# MONOPLACA_FINAL.net
KiCad netlist of a schematic drawn in Altium Designer
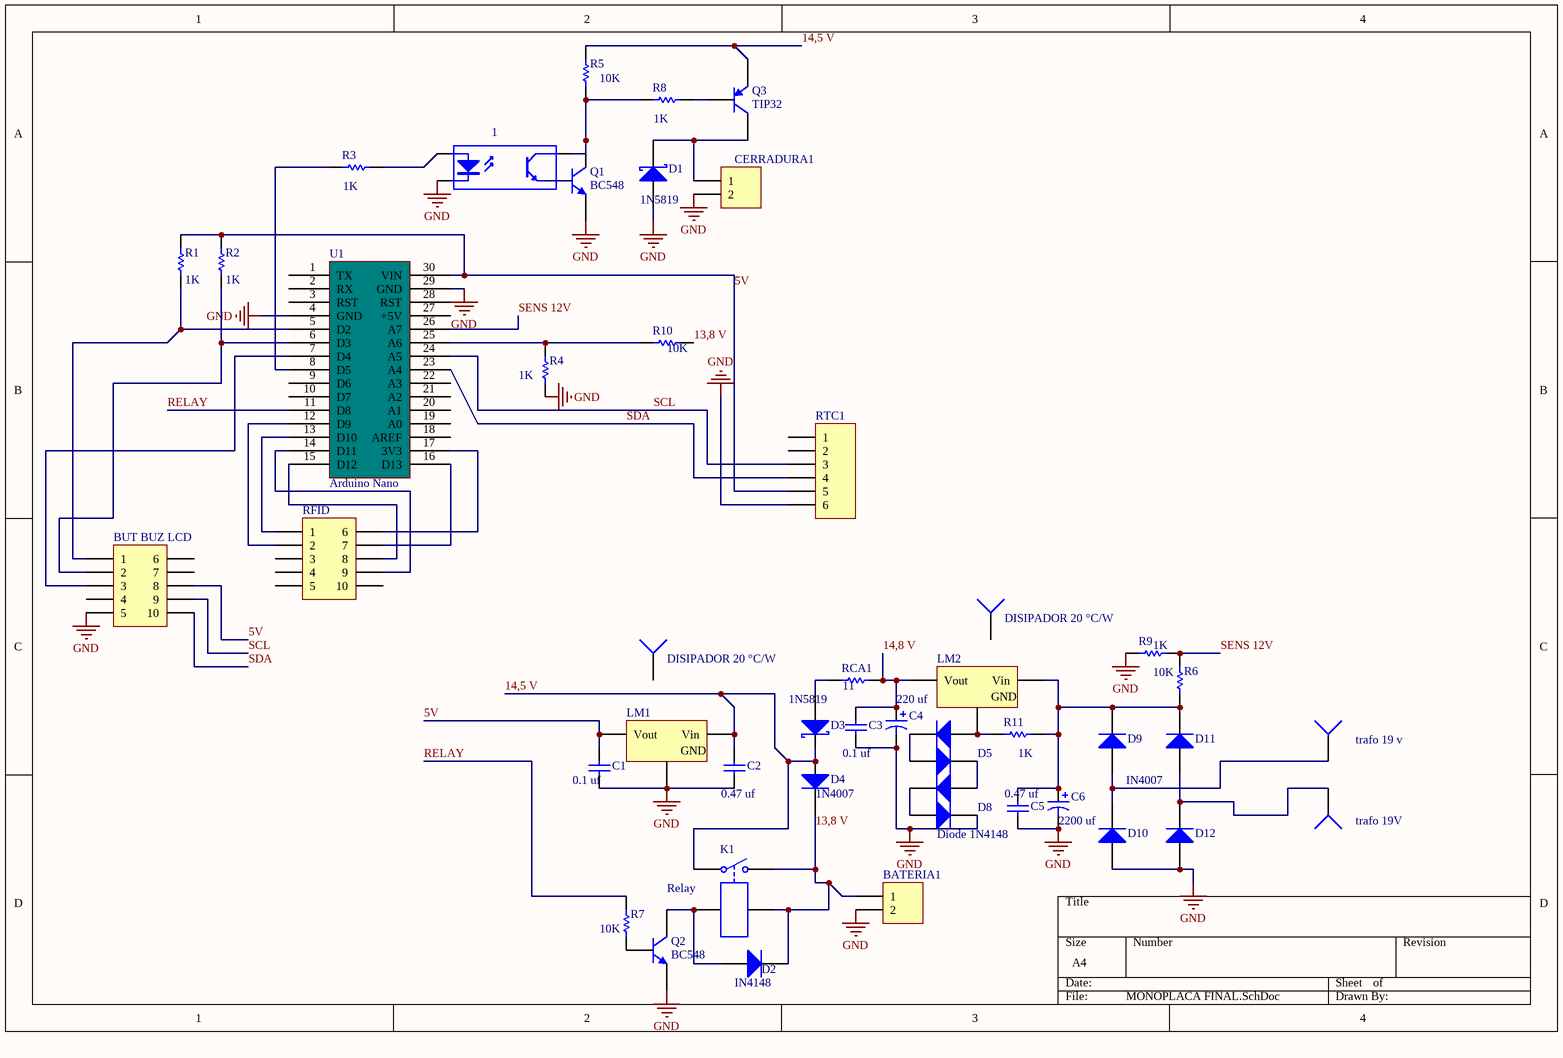
[diagram p0: MONOPLACA FINAL.SchDoc]

(export (version "E")
  (design (tool "Eeschema 10.0.6"))
  (components
    (comp (ref "1")
      (value "4N25")
      (footprint "DIP-6")
      (description "4-Pin Phototransistor Optocoupler")
      (fields (field (name "PUBLISHER") "Altium Limited"))
      (libsource (lib "altium-import") (part "root_0_Optoisolator1_"))
    )
    (comp (ref "BATERIA1")
      (value "Header 2")
      (footprint "Bornera 2 pin")
      (description "Header, 2-Pin")
      (fields (field (name "PUBLISHER") "Altium Limited"))
      (libsource (lib "Miscellaneous Connectors") (part "Header 2"))
    )
    (comp (ref "BUT BUZ LCD")
      (value "Header 5X2A")
      (footprint "HDR2X5_CEN")
      (description "Header, 5-Pin, Dual row")
      (fields (field (name "PUBLISHER") "Altium Limited"))
      (libsource (lib "Miscellaneous Connectors") (part "Header 5X2A"))
    )
    (comp (ref "C1")
      (value "0.1 uf")
      (footprint "CAP 5x12 mm")
      (description "Capacitor")
      (fields (field (name "Comment") "Cap") (field (name "PUBLISHER") "Altium Limited"))
      (libsource (lib "Miscellaneous Devices") (part "Cap"))
    )
    (comp (ref "C2")
      (value "0.47 uf")
      (footprint "CAP 12x10 mm")
      (description "Capacitor")
      (fields (field (name "Comment") "Cap") (field (name "PUBLISHER") "Altium Limited"))
      (libsource (lib "Miscellaneous Devices") (part "Cap"))
    )
    (comp (ref "C3")
      (value "0.1 uf")
      (footprint "CAP 5x12 mm")
      (description "Capacitor")
      (fields (field (name "Comment") "Cap") (field (name "PUBLISHER") "Altium Limited"))
      (libsource (lib "Miscellaneous Devices") (part "Cap"))
    )
    (comp (ref "C4")
      (value "220 uf")
      (footprint "CAP POL 3 - 8 mm")
      (description "Polarized Capacitor (Radial)")
      (fields (field (name "Comment") "Cap Pol1") (field (name "PUBLISHER") "Altium Limited"))
      (libsource (lib "Miscellaneous Devices") (part "Cap Pol1"))
    )
    (comp (ref "C5")
      (value "0.47 uf")
      (footprint "CAP 12x10 mm")
      (description "Capacitor")
      (fields (field (name "Comment") "Cap") (field (name "PUBLISHER") "Altium Limited"))
      (libsource (lib "Miscellaneous Devices") (part "Cap"))
    )
    (comp (ref "C6")
      (value "2200 uf")
      (footprint "CAP POL 18x7 mm")
      (description "Polarized Capacitor (Radial)")
      (fields (field (name "Comment") "Cap Pol1") (field (name "PUBLISHER") "Altium Limited"))
      (libsource (lib "Miscellaneous Devices") (part "Cap Pol1"))
    )
    (comp (ref "CERRADURA1")
      (value "Header 2")
      (footprint "Bornera 2 pin")
      (description "Header, 2-Pin")
      (fields (field (name "PUBLISHER") "Altium Limited"))
      (libsource (lib "Miscellaneous Connectors") (part "Header 2"))
    )
    (comp (ref "D1")
      (value "1N5819")
      (footprint "DO-41")
      (description "Schottky Diode")
      (fields (field (name "PUBLISHER") "Altium Limited"))
      (libsource (lib "Miscellaneous Devices") (part "D Schottky"))
    )
    (comp (ref "D2")
      (value "IN4148")
      (footprint "DO-35")
      (description "High Conductance Fast Diode")
      (fields (field (name "PUBLISHER") "Altium Limited"))
      (libsource (lib "Miscellaneous Devices") (part "Diode 1N914"))
    )
    (comp (ref "D3")
      (value "1N5819")
      (footprint "DO-41")
      (description "Schottky Diode")
      (fields (field (name "PUBLISHER") "Altium Limited"))
      (libsource (lib "Miscellaneous Devices") (part "D Schottky"))
    )
    (comp (ref "D4")
      (value "1N4007")
      (footprint "DO-41")
      (description "High Conductance Fast Diode")
      (fields (field (name "PUBLISHER") "Altium Limited"))
      (libsource (lib "Miscellaneous Devices") (part "Diode 1N914"))
    )
    (comp (ref "D5")
      (value "Diode 1N914")
      (footprint "DO-35")
      (description "High Conductance Fast Diode")
      (fields (field (name "PUBLISHER") "Altium Limited"))
      (libsource (lib "Miscellaneous Devices") (part "Diode 1N914"))
    )
    (comp (ref "D6")
      (value "Diode 1N914")
      (footprint "DO-35")
      (description "High Conductance Fast Diode")
      (fields (field (name "PUBLISHER") "Altium Limited"))
      (libsource (lib "Miscellaneous Devices") (part "Diode 1N914"))
    )
    (comp (ref "D7")
      (value "Diode 1N914")
      (footprint "DO-35")
      (description "High Conductance Fast Diode")
      (fields (field (name "PUBLISHER") "Altium Limited"))
      (libsource (lib "Miscellaneous Devices") (part "Diode 1N914"))
    )
    (comp (ref "D8")
      (value "Diode 1N4148")
      (footprint "DO-35")
      (description "High Conductance Fast Diode")
      (fields (field (name "PUBLISHER") "Altium Limited"))
      (libsource (lib "Miscellaneous Devices") (part "Diode 1N914"))
    )
    (comp (ref "D9")
      (value "IN4007")
      (footprint "DO-41")
      (description "High Conductance Fast Diode")
      (fields (field (name "PUBLISHER") "Altium Limited"))
      (libsource (lib "Miscellaneous Devices") (part "Diode 1N914"))
    )
    (comp (ref "D10")
      (value "IN4007")
      (footprint "DO-41")
      (description "High Conductance Fast Diode")
      (fields (field (name "PUBLISHER") "Altium Limited"))
      (libsource (lib "Miscellaneous Devices") (part "Diode 1N914"))
    )
    (comp (ref "D11")
      (value "IN4007")
      (footprint "DO-41")
      (description "High Conductance Fast Diode")
      (fields (field (name "PUBLISHER") "Altium Limited"))
      (libsource (lib "Miscellaneous Devices") (part "Diode 1N914"))
    )
    (comp (ref "D12")
      (value "IN4007")
      (footprint "DO-41")
      (description "High Conductance Fast Diode")
      (fields (field (name "PUBLISHER") "Altium Limited"))
      (libsource (lib "Miscellaneous Devices") (part "Diode 1N914"))
    )
    (comp (ref "DISIPADOR 1")
      (value "DISIPADOR 20 °C/W")
      (footprint "DISIPADOR 20 C°/W")
      (description "Socket")
      (fields (field (name "PUBLISHER") "Altium Limited"))
      (libsource (lib "Miscellaneous Connectors") (part "Socket"))
    )
    (comp (ref "DISIPADOR 2")
      (value "DISIPADOR 20 °C/W")
      (footprint "DISIPADOR 20 C°/W")
      (description "Socket")
      (fields (field (name "PUBLISHER") "Altium Limited"))
      (libsource (lib "Miscellaneous Connectors") (part "Socket"))
    )
    (comp (ref "J1")
      (value "trafo 19V")
      (footprint "PIN1")
      (description "Socket")
      (fields (field (name "PUBLISHER") "Altium Limited"))
      (libsource (lib "Miscellaneous Connectors") (part "Socket"))
    )
    (comp (ref "J2")
      (value "trafo 19 v")
      (footprint "PIN1")
      (description "Socket")
      (fields (field (name "PUBLISHER") "Altium Limited"))
      (libsource (lib "Miscellaneous Connectors") (part "Socket"))
    )
    (comp (ref "K1")
      (value "Relay")
      (footprint "RELE")
      (description "Single-Pole Single-Throw Relay")
      (fields (field (name "PUBLISHER") "Altium Limited"))
      (libsource (lib "Miscellaneous Devices") (part "Relay-SPST"))
    )
    (comp (ref "LM1")
      (value "LM7805")
      (footprint "TO-220AB")
      (description "Voltage Regulator")
      (fields (field (name "PUBLISHER") "Altium Limited"))
      (libsource (lib "Miscellaneous Devices") (part "Volt Reg"))
    )
    (comp (ref "LM2")
      (value "LM7812")
      (footprint "TO-220AB")
      (description "Voltage Regulator")
      (fields (field (name "PUBLISHER") "Altium Limited"))
      (libsource (lib "Miscellaneous Devices") (part "Volt Reg"))
    )
    (comp (ref "Q1")
      (value "BC548")
      (footprint "TO-92-MOD")
      (description "NPN General Purpose Amplifier")
      (fields (field (name "PUBLISHER") "Altium Limited"))
      (libsource (lib "Miscellaneous Devices") (part "2N3904"))
    )
    (comp (ref "Q2")
      (value "BC548")
      (footprint "TO-92-MOD")
      (description "NPN Bipolar Transistor")
      (fields (field (name "PUBLISHER") "Altium Limited"))
      (libsource (lib "Miscellaneous Devices") (part "NPN"))
    )
    (comp (ref "Q3")
      (value "TIP32")
      (footprint "TO-220AB")
      (description "PNP General Purpose Amplifier")
      (fields (field (name "PUBLISHER") "Altium Limited"))
      (libsource (lib "Miscellaneous Devices") (part "2N3906"))
    )
    (comp (ref "R1")
      (value "1K")
      (footprint "RESISTENCIA 0.25 W")
      (description "Resistor")
      (fields (field (name "Comment") "Res1") (field (name "PUBLISHER") "Altium Limited"))
      (libsource (lib "Miscellaneous Devices") (part "Res1"))
    )
    (comp (ref "R2")
      (value "1K")
      (footprint "RESISTENCIA 0.25 W")
      (description "Resistor")
      (fields (field (name "Comment") "Res1") (field (name "PUBLISHER") "Altium Limited"))
      (libsource (lib "Miscellaneous Devices") (part "Res1"))
    )
    (comp (ref "R3")
      (value "1K")
      (footprint "RESISTENCIA 0.25 W")
      (description "Resistor")
      (fields (field (name "Comment") "Res1") (field (name "PUBLISHER") "Altium Limited"))
      (libsource (lib "Miscellaneous Devices") (part "Res1"))
    )
    (comp (ref "R4")
      (value "1K")
      (footprint "RESISTENCIA 0.25 W")
      (description "Resistor")
      (fields (field (name "Comment") "Res1") (field (name "PUBLISHER") "Altium Limited"))
      (libsource (lib "Miscellaneous Devices") (part "Res1"))
    )
    (comp (ref "R5")
      (value "10K")
      (footprint "RESISTENCIA 0.25 W")
      (description "Resistor")
      (fields (field (name "Comment") "Res1") (field (name "PUBLISHER") "Altium Limited"))
      (libsource (lib "Miscellaneous Devices") (part "Res1"))
    )
    (comp (ref "R6")
      (value "10K")
      (footprint "RESISTENCIA 0.25 W")
      (description "Resistor")
      (fields (field (name "Comment") "Res1") (field (name "PUBLISHER") "Altium Limited"))
      (libsource (lib "Miscellaneous Devices") (part "Res1"))
    )
    (comp (ref "R7")
      (value "10K")
      (footprint "RESISTENCIA 0.25 W")
      (description "Resistor")
      (fields (field (name "Comment") "Res1") (field (name "PUBLISHER") "Altium Limited"))
      (libsource (lib "Miscellaneous Devices") (part "Res1"))
    )
    (comp (ref "R8")
      (value "1K")
      (footprint "RESISTENCIA 0.25 W")
      (description "Resistor")
      (fields (field (name "Comment") "Res1") (field (name "PUBLISHER") "Altium Limited"))
      (libsource (lib "Miscellaneous Devices") (part "Res1"))
    )
    (comp (ref "R9")
      (value "1K")
      (footprint "RESISTENCIA 0.25 W")
      (description "Resistor")
      (fields (field (name "Comment") "Res1") (field (name "PUBLISHER") "Altium Limited"))
      (libsource (lib "Miscellaneous Devices") (part "Res1"))
    )
    (comp (ref "R10")
      (value "10K")
      (footprint "RESISTENCIA 0.25 W")
      (description "Resistor")
      (fields (field (name "Comment") "Res1") (field (name "PUBLISHER") "Altium Limited"))
      (libsource (lib "Miscellaneous Devices") (part "Res1"))
    )
    (comp (ref "R11")
      (value "1K")
      (footprint "RESISTENCIA 0.25 W")
      (description "Resistor")
      (fields (field (name "Comment") "Res1") (field (name "PUBLISHER") "Altium Limited"))
      (libsource (lib "Miscellaneous Devices") (part "Res1"))
    )
    (comp (ref "RCA1")
      (value "11")
      (footprint "RESISTENCIA 5W")
      (description "Resistor")
      (fields (field (name "Comment") "Res1") (field (name "PUBLISHER") "Altium Limited"))
      (libsource (lib "Miscellaneous Devices") (part "Res1"))
    )
    (comp (ref "RFID")
      (value "Header 5X2A")
      (footprint "HDR2X5_CEN")
      (description "Header, 5-Pin, Dual row")
      (fields (field (name "PUBLISHER") "Altium Limited"))
      (libsource (lib "Miscellaneous Connectors") (part "Header 5X2A"))
    )
    (comp (ref "RTC1")
      (value "Header 6")
      (footprint "HDR1X6")
      (description "Header, 6-Pin")
      (fields (field (name "PUBLISHER") "Altium Limited"))
      (libsource (lib "Miscellaneous Connectors") (part "Header 6"))
    )
    (comp (ref "U1")
      (value "Arduino Nano")
      (footprint "Arduino nano")
      (libsource (lib "Nano") (part "Component_1"))
    )
  )
  (nets
    (net (code "1") (name "/5V") (class "Default")
      (node (ref "BUT BUZ LCD") (pin "8") (pinfunction "8_8") (pintype "passive"))
      (node (ref "C1") (pin "2") (pinfunction "2_2") (pintype "passive"))
      (node (ref "LM1") (pin "3") (pinfunction "Vout_3") (pintype "passive"))
      (node (ref "R1") (pin "2") (pinfunction "2_2") (pintype "passive"))
      (node (ref "R2") (pin "2") (pinfunction "2_2") (pintype "passive"))
      (node (ref "RTC1") (pin "5") (pinfunction "5_5") (pintype "passive"))
      (node (ref "U1") (pin "30") (pinfunction "VIN_30") (pintype "passive"))
    )
    (net (code "2") (name "/13,8 V") (class "Default")
      (node (ref "BATERIA1") (pin "1") (pinfunction "1_1") (pintype "passive"))
      (node (ref "D2") (pin "2") (pinfunction "K_2") (pintype "passive"))
      (node (ref "D4") (pin "2") (pinfunction "K_2") (pintype "passive"))
      (node (ref "K1") (pin "2") (pinfunction "2_2") (pintype "passive"))
      (node (ref "K1") (pin "4") (pinfunction "4_4") (pintype "passive"))
      (node (ref "R10") (pin "2") (pinfunction "2_2") (pintype "passive"))
    )
    (net (code "3") (name "/14,5 V") (class "Default")
      (node (ref "C2") (pin "2") (pinfunction "2_2") (pintype "passive"))
      (node (ref "D3") (pin "2") (pinfunction "K_2") (pintype "passive"))
      (node (ref "D4") (pin "1") (pinfunction "A_1") (pintype "passive"))
      (node (ref "K1") (pin "1") (pinfunction "1_1") (pintype "passive"))
      (node (ref "LM1") (pin "1") (pinfunction "Vin_1") (pintype "passive"))
      (node (ref "Q3") (pin "1") (pinfunction "E_1") (pintype "passive"))
      (node (ref "R5") (pin "2") (pinfunction "2_2") (pintype "passive"))
    )
    (net (code "4") (name "/14,8 V") (class "Default")
      (node (ref "C3") (pin "2") (pinfunction "2_2") (pintype "passive"))
      (node (ref "C4") (pin "1") (pinfunction "1_1") (pintype "passive"))
      (node (ref "LM2") (pin "3") (pinfunction "Vout_3") (pintype "passive"))
      (node (ref "RCA1") (pin "2") (pinfunction "2_2") (pintype "passive"))
    )
    (net (code "5") (name "/RELAY") (class "Default")
      (node (ref "R7") (pin "1") (pinfunction "1_1") (pintype "passive"))
      (node (ref "U1") (pin "11") (pinfunction "D8_11") (pintype "passive"))
    )
    (net (code "6") (name "/SCL") (class "Default")
      (node (ref "BUT BUZ LCD") (pin "9") (pinfunction "9_9") (pintype "passive"))
      (node (ref "RTC1") (pin "3") (pinfunction "3_3") (pintype "passive"))
      (node (ref "U1") (pin "24") (pinfunction "A5_24") (pintype "passive"))
    )
    (net (code "7") (name "/SDA") (class "Default")
      (node (ref "BUT BUZ LCD") (pin "10") (pinfunction "10_10") (pintype "passive"))
      (node (ref "RTC1") (pin "4") (pinfunction "4_4") (pintype "passive"))
      (node (ref "U1") (pin "23") (pinfunction "A4_23") (pintype "passive"))
    )
    (net (code "8") (name "/SENS 12V") (class "Default")
      (node (ref "R6") (pin "2") (pinfunction "2_2") (pintype "passive"))
      (node (ref "R9") (pin "2") (pinfunction "2_2") (pintype "passive"))
      (node (ref "U1") (pin "26") (pinfunction "A7_26") (pintype "passive"))
    )
    (net (code "9") (name "GND") (class "Default")
      (node (ref "1") (pin "2") (pinfunction "K_2") (pintype "passive"))
      (node (ref "BATERIA1") (pin "2") (pinfunction "2_2") (pintype "passive"))
      (node (ref "BUT BUZ LCD") (pin "5") (pinfunction "5_5") (pintype "passive"))
      (node (ref "C1") (pin "1") (pinfunction "1_1") (pintype "passive"))
      (node (ref "C2") (pin "1") (pinfunction "1_1") (pintype "passive"))
      (node (ref "C3") (pin "1") (pinfunction "1_1") (pintype "passive"))
      (node (ref "C4") (pin "2") (pinfunction "2_2") (pintype "passive"))
      (node (ref "C5") (pin "1") (pinfunction "1_1") (pintype "passive"))
      (node (ref "C6") (pin "2") (pinfunction "2_2") (pintype "passive"))
      (node (ref "CERRADURA1") (pin "2") (pinfunction "2_2") (pintype "passive"))
      (node (ref "D1") (pin "1") (pinfunction "A_1") (pintype "passive"))
      (node (ref "D10") (pin "1") (pinfunction "A_1") (pintype "passive"))
      (node (ref "D12") (pin "1") (pinfunction "A_1") (pintype "passive"))
      (node (ref "D8") (pin "2") (pinfunction "K_2") (pintype "passive"))
      (node (ref "LM1") (pin "2") (pinfunction "GND_2") (pintype "passive"))
      (node (ref "Q1") (pin "1") (pinfunction "E_1") (pintype "passive"))
      (node (ref "Q2") (pin "3") (pinfunction "E_3") (pintype "passive"))
      (node (ref "R4") (pin "1") (pinfunction "1_1") (pintype "passive"))
      (node (ref "R9") (pin "1") (pinfunction "1_1") (pintype "passive"))
      (node (ref "RTC1") (pin "6") (pinfunction "6_6") (pintype "passive"))
      (node (ref "U1") (pin "29") (pinfunction "GND_29") (pintype "passive"))
      (node (ref "U1") (pin "4") (pinfunction "GND_4") (pintype "passive"))
    )
    (net (code "10") (name "Net-(1-A)") (class "Default")
      (node (ref "1") (pin "1") (pinfunction "A_1") (pintype "passive"))
      (node (ref "R3") (pin "2") (pinfunction "2_2") (pintype "passive"))
    )
    (net (code "11") (name "Net-(1-C)") (class "Default")
      (node (ref "1") (pin "4") (pinfunction "C_4") (pintype "passive"))
      (node (ref "Q1") (pin "3") (pinfunction "C_3") (pintype "passive"))
      (node (ref "R5") (pin "1") (pinfunction "1_1") (pintype "passive"))
      (node (ref "R8") (pin "1") (pinfunction "1_1") (pintype "passive"))
    )
    (net (code "12") (name "Net-(1-E)") (class "Default")
      (node (ref "1") (pin "3") (pinfunction "E_3") (pintype "passive"))
      (node (ref "Q1") (pin "2") (pinfunction "B_2") (pintype "passive"))
    )
    (net (code "13") (name "Net-(D1-K)") (class "Default")
      (node (ref "CERRADURA1") (pin "1") (pinfunction "1_1") (pintype "passive"))
      (node (ref "D1") (pin "2") (pinfunction "K_2") (pintype "passive"))
      (node (ref "Q3") (pin "3") (pinfunction "C_3") (pintype "passive"))
    )
    (net (code "14") (name "Net-(D2-A)") (class "Default")
      (node (ref "D2") (pin "1") (pinfunction "A_1") (pintype "passive"))
      (node (ref "K1") (pin "3") (pinfunction "3_3") (pintype "passive"))
      (node (ref "Q2") (pin "1") (pinfunction "C_1") (pintype "passive"))
    )
    (net (code "15") (name "Net-(D3-A)") (class "Default")
      (node (ref "D3") (pin "1") (pinfunction "A_1") (pintype "passive"))
      (node (ref "RCA1") (pin "1") (pinfunction "1_1") (pintype "passive"))
    )
    (net (code "16") (name "Net-(D5-A)") (class "Default")
      (node (ref "D5") (pin "1") (pinfunction "A_1") (pintype "passive"))
      (node (ref "LM2") (pin "2") (pinfunction "GND_2") (pintype "passive"))
      (node (ref "R11") (pin "1") (pinfunction "1_1") (pintype "passive"))
    )
    (net (code "17") (name "Net-(D5-K)") (class "Default")
      (node (ref "D5") (pin "2") (pinfunction "K_2") (pintype "passive"))
      (node (ref "D6") (pin "1") (pinfunction "A_1") (pintype "passive"))
    )
    (net (code "18") (name "Net-(D6-K)") (class "Default")
      (node (ref "D6") (pin "2") (pinfunction "K_2") (pintype "passive"))
      (node (ref "D7") (pin "1") (pinfunction "A_1") (pintype "passive"))
    )
    (net (code "19") (name "Net-(D7-K)") (class "Default")
      (node (ref "D7") (pin "2") (pinfunction "K_2") (pintype "passive"))
      (node (ref "D8") (pin "1") (pinfunction "A_1") (pintype "passive"))
    )
    (net (code "20") (name "Net-(D10-K)") (class "Default")
      (node (ref "D10") (pin "2") (pinfunction "K_2") (pintype "passive"))
      (node (ref "D9") (pin "1") (pinfunction "A_1") (pintype "passive"))
      (node (ref "J2") (pin "1") (pinfunction "1_1") (pintype "passive"))
    )
    (net (code "21") (name "Net-(D11-A)") (class "Default")
      (node (ref "D11") (pin "1") (pinfunction "A_1") (pintype "passive"))
      (node (ref "D12") (pin "2") (pinfunction "K_2") (pintype "passive"))
      (node (ref "J1") (pin "1") (pinfunction "1_1") (pintype "passive"))
    )
    (net (code "22") (name "Net-(D11-K)") (class "Default")
      (node (ref "C5") (pin "2") (pinfunction "2_2") (pintype "passive"))
      (node (ref "C6") (pin "1") (pinfunction "1_1") (pintype "passive"))
      (node (ref "D11") (pin "2") (pinfunction "K_2") (pintype "passive"))
      (node (ref "D9") (pin "2") (pinfunction "K_2") (pintype "passive"))
      (node (ref "LM2") (pin "1") (pinfunction "Vin_1") (pintype "passive"))
      (node (ref "R11") (pin "2") (pinfunction "2_2") (pintype "passive"))
      (node (ref "R6") (pin "1") (pinfunction "1_1") (pintype "passive"))
    )
    (net (code "23") (name "Net-(Q2-B)") (class "Default")
      (node (ref "Q2") (pin "2") (pinfunction "B_2") (pintype "passive"))
      (node (ref "R7") (pin "2") (pinfunction "2_2") (pintype "passive"))
    )
    (net (code "24") (name "Net-(Q3-B)") (class "Default")
      (node (ref "Q3") (pin "2") (pinfunction "B_2") (pintype "passive"))
      (node (ref "R8") (pin "2") (pinfunction "2_2") (pintype "passive"))
    )
    (net (code "25") (name "Net-(U1-3V3)") (class "Default")
      (node (ref "RFID") (pin "6") (pinfunction "6_6") (pintype "passive"))
      (node (ref "U1") (pin "17") (pinfunction "3V3_17") (pintype "passive"))
    )
    (net (code "26") (name "Net-(U1-A6)") (class "Default")
      (node (ref "R10") (pin "1") (pinfunction "1_1") (pintype "passive"))
      (node (ref "R4") (pin "2") (pinfunction "2_2") (pintype "passive"))
      (node (ref "U1") (pin "25") (pinfunction "A6_25") (pintype "passive"))
    )
    (net (code "27") (name "Net-(U1-D2)") (class "Default")
      (node (ref "BUT BUZ LCD") (pin "1") (pinfunction "1_1") (pintype "passive"))
      (node (ref "R1") (pin "1") (pinfunction "1_1") (pintype "passive"))
      (node (ref "U1") (pin "5") (pinfunction "D2_5") (pintype "passive"))
    )
    (net (code "28") (name "Net-(U1-D3)") (class "Default")
      (node (ref "BUT BUZ LCD") (pin "2") (pinfunction "2_2") (pintype "passive"))
      (node (ref "R2") (pin "1") (pinfunction "1_1") (pintype "passive"))
      (node (ref "U1") (pin "6") (pinfunction "D3_6") (pintype "passive"))
    )
    (net (code "29") (name "Net-(U1-D4)") (class "Default")
      (node (ref "BUT BUZ LCD") (pin "3") (pinfunction "3_3") (pintype "passive"))
      (node (ref "U1") (pin "7") (pinfunction "D4_7") (pintype "passive"))
    )
    (net (code "30") (name "Net-(U1-D5)") (class "Default")
      (node (ref "R3") (pin "1") (pinfunction "1_1") (pintype "passive"))
      (node (ref "U1") (pin "8") (pinfunction "D5_8") (pintype "passive"))
    )
    (net (code "31") (name "Net-(U1-D9)") (class "Default")
      (node (ref "RFID") (pin "2") (pinfunction "2_2") (pintype "passive"))
      (node (ref "U1") (pin "12") (pinfunction "D9_12") (pintype "passive"))
    )
    (net (code "32") (name "Net-(U1-D10)") (class "Default")
      (node (ref "RFID") (pin "1") (pinfunction "1_1") (pintype "passive"))
      (node (ref "U1") (pin "13") (pinfunction "D10_13") (pintype "passive"))
    )
    (net (code "33") (name "Net-(U1-D11)") (class "Default")
      (node (ref "RFID") (pin "9") (pinfunction "9_9") (pintype "passive"))
      (node (ref "U1") (pin "14") (pinfunction "D11_14") (pintype "passive"))
    )
    (net (code "34") (name "Net-(U1-D12)") (class "Default")
      (node (ref "RFID") (pin "8") (pinfunction "8_8") (pintype "passive"))
      (node (ref "U1") (pin "15") (pinfunction "D12_15") (pintype "passive"))
    )
    (net (code "35") (name "Net-(U1-D13)") (class "Default")
      (node (ref "RFID") (pin "7") (pinfunction "7_7") (pintype "passive"))
      (node (ref "U1") (pin "16") (pinfunction "D13_16") (pintype "passive"))
    )
    (net (code "36") (name "unconnected-(BUT BUZ LCD-Pad4)") (class "Default")
      (node (ref "BUT BUZ LCD") (pin "4") (pinfunction "4_4") (pintype "passive"))
    )
    (net (code "37") (name "unconnected-(BUT BUZ LCD-Pad6)") (class "Default")
      (node (ref "BUT BUZ LCD") (pin "6") (pinfunction "6_6") (pintype "passive"))
    )
    (net (code "38") (name "unconnected-(BUT BUZ LCD-Pad7)") (class "Default")
      (node (ref "BUT BUZ LCD") (pin "7") (pinfunction "7_7") (pintype "passive"))
    )
    (net (code "39") (name "unconnected-(DISIPADOR 1-Pad1)") (class "Default")
      (node (ref "DISIPADOR 1") (pin "1") (pinfunction "1_1") (pintype "passive"))
    )
    (net (code "40") (name "unconnected-(DISIPADOR 2-Pad1)") (class "Default")
      (node (ref "DISIPADOR 2") (pin "1") (pinfunction "1_1") (pintype "passive"))
    )
    (net (code "41") (name "unconnected-(RFID-Pad3)") (class "Default")
      (node (ref "RFID") (pin "3") (pinfunction "3_3") (pintype "passive"))
    )
    (net (code "42") (name "unconnected-(RFID-Pad4)") (class "Default")
      (node (ref "RFID") (pin "4") (pinfunction "4_4") (pintype "passive"))
    )
    (net (code "43") (name "unconnected-(RFID-Pad5)") (class "Default")
      (node (ref "RFID") (pin "5") (pinfunction "5_5") (pintype "passive"))
    )
    (net (code "44") (name "unconnected-(RFID-Pad10)") (class "Default")
      (node (ref "RFID") (pin "10") (pinfunction "10_10") (pintype "passive"))
    )
    (net (code "45") (name "unconnected-(RTC1-Pad1)") (class "Default")
      (node (ref "RTC1") (pin "1") (pinfunction "1_1") (pintype "passive"))
    )
    (net (code "46") (name "unconnected-(RTC1-Pad2)") (class "Default")
      (node (ref "RTC1") (pin "2") (pinfunction "2_2") (pintype "passive"))
    )
    (net (code "47") (name "unconnected-(U1-+5V-Pad27)") (class "Default")
      (node (ref "U1") (pin "27") (pinfunction "+5V_27") (pintype "passive"))
    )
    (net (code "48") (name "unconnected-(U1-A0-Pad19)") (class "Default")
      (node (ref "U1") (pin "19") (pinfunction "A0_19") (pintype "passive"))
    )
    (net (code "49") (name "unconnected-(U1-A1-Pad20)") (class "Default")
      (node (ref "U1") (pin "20") (pinfunction "A1_20") (pintype "passive"))
    )
    (net (code "50") (name "unconnected-(U1-A2-Pad21)") (class "Default")
      (node (ref "U1") (pin "21") (pinfunction "A2_21") (pintype "passive"))
    )
    (net (code "51") (name "unconnected-(U1-A3-Pad22)") (class "Default")
      (node (ref "U1") (pin "22") (pinfunction "A3_22") (pintype "passive"))
    )
    (net (code "52") (name "unconnected-(U1-AREF-Pad18)") (class "Default")
      (node (ref "U1") (pin "18") (pinfunction "AREF_18") (pintype "passive"))
    )
    (net (code "53") (name "unconnected-(U1-D6-Pad9)") (class "Default")
      (node (ref "U1") (pin "9") (pinfunction "D6_9") (pintype "passive"))
    )
    (net (code "54") (name "unconnected-(U1-D7-Pad10)") (class "Default")
      (node (ref "U1") (pin "10") (pinfunction "D7_10") (pintype "passive"))
    )
    (net (code "55") (name "unconnected-(U1-RST-Pad3)") (class "Default")
      (node (ref "U1") (pin "3") (pinfunction "RST_3") (pintype "passive"))
    )
    (net (code "56") (name "unconnected-(U1-RST-Pad28)") (class "Default")
      (node (ref "U1") (pin "28") (pinfunction "RST_28") (pintype "passive"))
    )
    (net (code "57") (name "unconnected-(U1-RX-Pad2)") (class "Default")
      (node (ref "U1") (pin "2") (pinfunction "RX_2") (pintype "passive"))
    )
    (net (code "58") (name "unconnected-(U1-TX-Pad1)") (class "Default")
      (node (ref "U1") (pin "1") (pinfunction "TX_1") (pintype "passive"))
    )
  )
)
